# vsauce.net
KiCad netlist of a schematic drawn in EAGLE
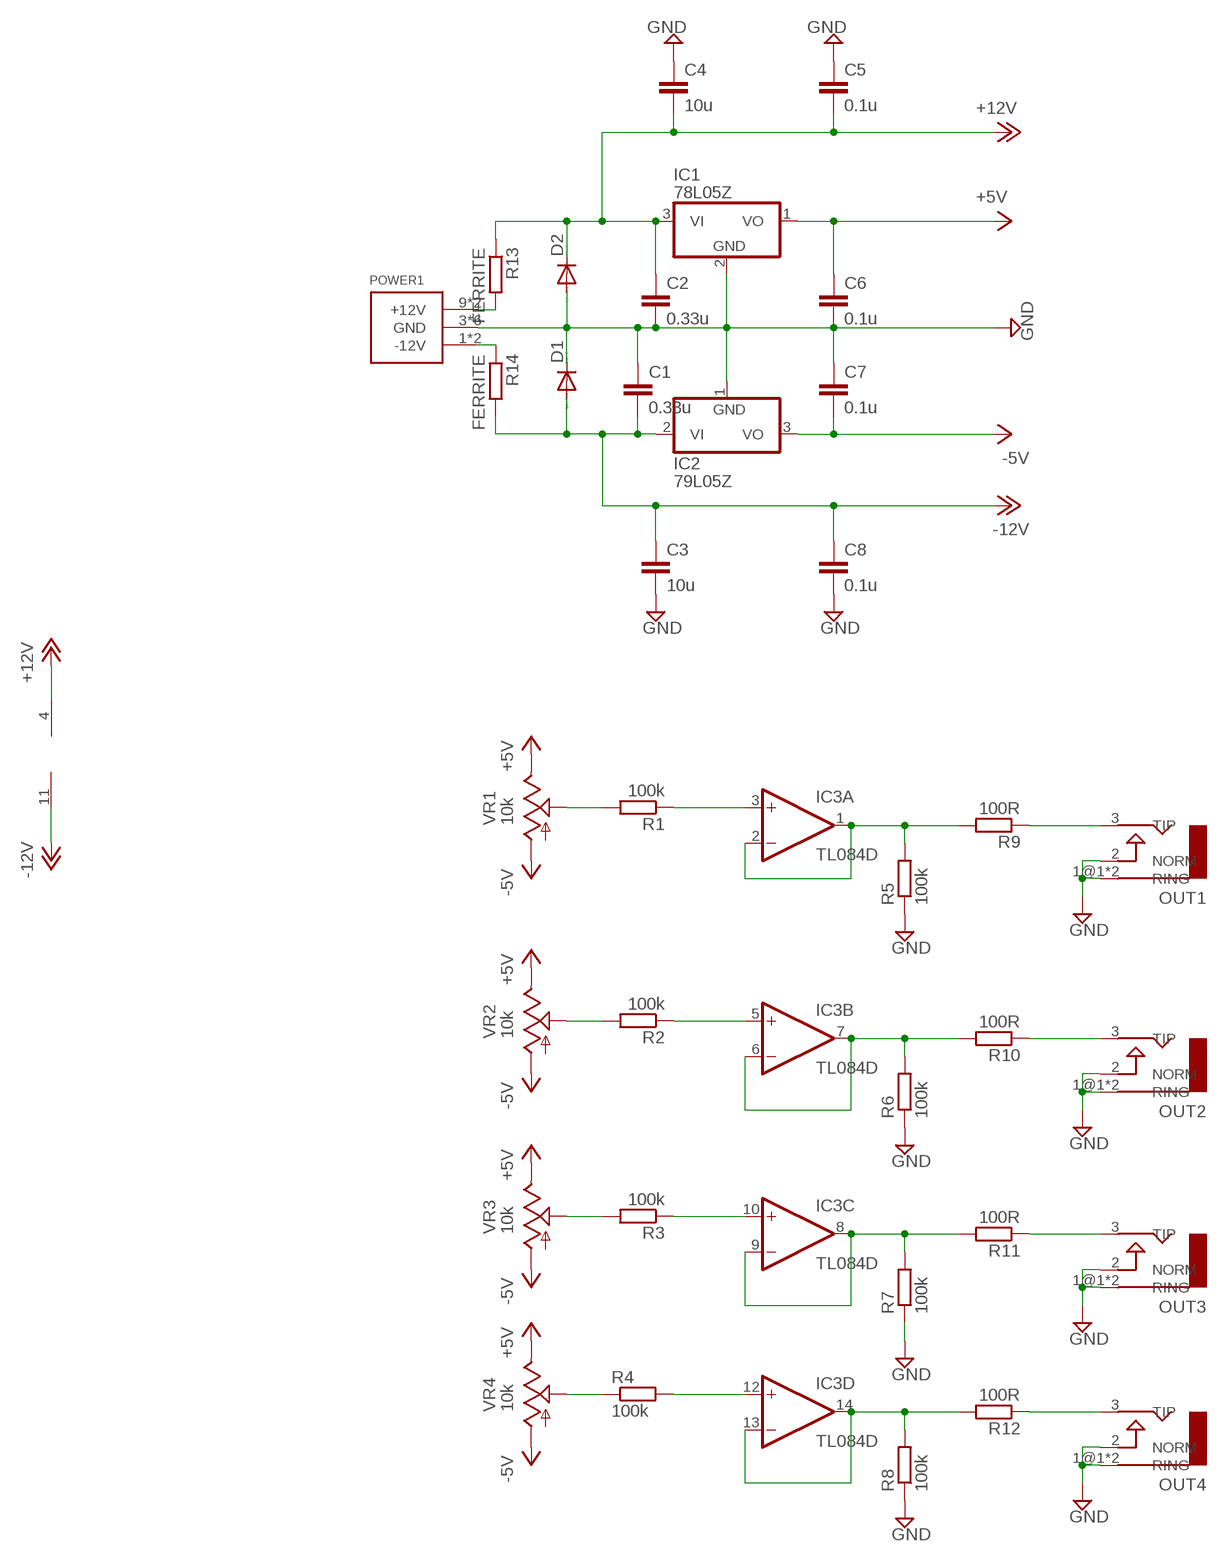
[diagram p0: schematic, sheet 1]

(export (version "E")
  (design (tool "Eeschema 10.0.6"))
  (components
    (comp (ref "C1")
      (value "0.33u")
      (footprint "eagle-import:C0805")
      (libsource (lib "eagle-import") (part "C-EUC0805"))
    )
    (comp (ref "C2")
      (value "0.33u")
      (footprint "eagle-import:C0805")
      (libsource (lib "eagle-import") (part "C-EUC0805"))
    )
    (comp (ref "C3")
      (value "10u")
      (footprint "eagle-import:C0805")
      (libsource (lib "eagle-import") (part "C-EUC0805"))
    )
    (comp (ref "C4")
      (value "10u")
      (footprint "eagle-import:C0805")
      (libsource (lib "eagle-import") (part "C-EUC0805"))
    )
    (comp (ref "C5")
      (value "0.1u")
      (footprint "eagle-import:C0805")
      (libsource (lib "eagle-import") (part "C-EUC0805"))
    )
    (comp (ref "C6")
      (value "0.1u")
      (footprint "eagle-import:C0805")
      (libsource (lib "eagle-import") (part "C-EUC0805"))
    )
    (comp (ref "C7")
      (value "0.1u")
      (footprint "eagle-import:C0805")
      (libsource (lib "eagle-import") (part "C-EUC0805"))
    )
    (comp (ref "C8")
      (value "0.1u")
      (footprint "eagle-import:C0805")
      (libsource (lib "eagle-import") (part "C-EUC0805"))
    )
    (comp (ref "D1")
      (value "DIODE-SOD323-W")
      (footprint "eagle-import:SOD323-W")
      (libsource (lib "eagle-import") (part "DIODE-SOD323-W"))
    )
    (comp (ref "D2")
      (value "DIODE-SOD323-W")
      (footprint "eagle-import:SOD323-W")
      (libsource (lib "eagle-import") (part "DIODE-SOD323-W"))
    )
    (comp (ref "IC1")
      (value "78L05Z")
      (footprint "eagle-import:TO92")
      (libsource (lib "eagle-import") (part "78ZL05"))
    )
    (comp (ref "IC2")
      (value "79L05Z")
      (footprint "eagle-import:TO92")
      (libsource (lib "eagle-import") (part "79L05"))
    )
    (comp (ref "IC3")
      (value "TL084D")
      (footprint "eagle-import:SO14")
      (libsource (lib "eagle-import") (part "TL084D"))
    )
    (comp (ref "OUT1")
      (value "V1")
      (footprint "eagle-import:ERTHENVAR-JACK")
      (libsource (lib "eagle-import") (part "AUDIO-JACKERTHENVAR"))
    )
    (comp (ref "OUT2")
      (value "V2")
      (footprint "eagle-import:ERTHENVAR-JACK")
      (libsource (lib "eagle-import") (part "AUDIO-JACKERTHENVAR"))
    )
    (comp (ref "OUT3")
      (value "V3")
      (footprint "eagle-import:ERTHENVAR-JACK")
      (libsource (lib "eagle-import") (part "AUDIO-JACKERTHENVAR"))
    )
    (comp (ref "OUT4")
      (value "V4")
      (footprint "eagle-import:ERTHENVAR-JACK")
      (libsource (lib "eagle-import") (part "AUDIO-JACKERTHENVAR"))
    )
    (comp (ref "POWER1")
      (value "POWER_SIMPLE10")
      (footprint "eagle-import:POWER_10")
      (libsource (lib "eagle-import") (part "POWER_SIMPLE10"))
    )
    (comp (ref "R1")
      (value "100k")
      (footprint "eagle-import:R0805")
      (libsource (lib "eagle-import") (part "R-EU_R0805"))
    )
    (comp (ref "R2")
      (value "100k")
      (footprint "eagle-import:R0805")
      (libsource (lib "eagle-import") (part "R-EU_R0805"))
    )
    (comp (ref "R3")
      (value "100k")
      (footprint "eagle-import:R0805")
      (libsource (lib "eagle-import") (part "R-EU_R0805"))
    )
    (comp (ref "R4")
      (value "100k")
      (footprint "eagle-import:R0805")
      (libsource (lib "eagle-import") (part "R-EU_R0805"))
    )
    (comp (ref "R5")
      (value "100k")
      (footprint "eagle-import:R0805")
      (libsource (lib "eagle-import") (part "R-EU_R0805"))
    )
    (comp (ref "R6")
      (value "100k")
      (footprint "eagle-import:R0805")
      (libsource (lib "eagle-import") (part "R-EU_R0805"))
    )
    (comp (ref "R7")
      (value "100k")
      (footprint "eagle-import:R0805")
      (libsource (lib "eagle-import") (part "R-EU_R0805"))
    )
    (comp (ref "R8")
      (value "100k")
      (footprint "eagle-import:R0805")
      (libsource (lib "eagle-import") (part "R-EU_R0805"))
    )
    (comp (ref "R9")
      (value "100R")
      (footprint "eagle-import:R0805")
      (libsource (lib "eagle-import") (part "R-EU_R0805"))
    )
    (comp (ref "R10")
      (value "100R")
      (footprint "eagle-import:R0805")
      (libsource (lib "eagle-import") (part "R-EU_R0805"))
    )
    (comp (ref "R11")
      (value "100R")
      (footprint "eagle-import:R0805")
      (libsource (lib "eagle-import") (part "R-EU_R0805"))
    )
    (comp (ref "R12")
      (value "100R")
      (footprint "eagle-import:R0805")
      (libsource (lib "eagle-import") (part "R-EU_R0805"))
    )
    (comp (ref "R13")
      (value "FERRITE")
      (footprint "eagle-import:R0805")
      (libsource (lib "eagle-import") (part "R-EU_R0805"))
    )
    (comp (ref "R14")
      (value "FERRITE")
      (footprint "eagle-import:R0805")
      (libsource (lib "eagle-import") (part "R-EU_R0805"))
    )
    (comp (ref "VR1")
      (value "10k")
      (footprint "eagle-import:9MM_SNAP-IN_POT")
      (libsource (lib "eagle-import") (part "9MM_SNAP-IN_POT_"))
    )
    (comp (ref "VR2")
      (value "10k")
      (footprint "eagle-import:9MM_SNAP-IN_POT")
      (libsource (lib "eagle-import") (part "9MM_SNAP-IN_POT_"))
    )
    (comp (ref "VR3")
      (value "10k")
      (footprint "eagle-import:9MM_SNAP-IN_POT")
      (libsource (lib "eagle-import") (part "9MM_SNAP-IN_POT_"))
    )
    (comp (ref "VR4")
      (value "10k")
      (footprint "eagle-import:9MM_SNAP-IN_POT")
      (libsource (lib "eagle-import") (part "9MM_SNAP-IN_POT_"))
    )
  )
  (nets
    (net (code "1") (name "+5V") (class "Default")
      (node (ref "C6") (pin "1") (pinfunction "1_1") (pintype "passive"))
      (node (ref "IC1") (pin "1") (pinfunction "VO_1") (pintype "passive"))
      (node (ref "VR1") (pin "3") (pinfunction "E_3") (pintype "passive"))
      (node (ref "VR2") (pin "3") (pinfunction "E_3") (pintype "passive"))
      (node (ref "VR3") (pin "3") (pinfunction "E_3") (pintype "passive"))
      (node (ref "VR4") (pin "3") (pinfunction "E_3") (pintype "passive"))
    )
    (net (code "2") (name "+12V") (class "Default")
      (node (ref "C2") (pin "1") (pinfunction "1_1") (pintype "passive"))
      (node (ref "C4") (pin "2") (pinfunction "2_2") (pintype "passive"))
      (node (ref "C5") (pin "2") (pinfunction "2_2") (pintype "passive"))
      (node (ref "D2") (pin "C") (pinfunction "C_C") (pintype "passive"))
      (node (ref "IC1") (pin "3") (pinfunction "VI_3") (pintype "input"))
      (node (ref "IC3") (pin "4") (pinfunction "V+_4") (pintype "power_in"))
      (node (ref "R13") (pin "1") (pinfunction "1_1") (pintype "passive"))
    )
    (net (code "3") (name "-5V") (class "Default")
      (node (ref "C7") (pin "2") (pinfunction "2_2") (pintype "passive"))
      (node (ref "IC2") (pin "3") (pinfunction "VO_3") (pintype "passive"))
      (node (ref "VR1") (pin "1") (pinfunction "A_1") (pintype "passive"))
      (node (ref "VR2") (pin "1") (pinfunction "A_1") (pintype "passive"))
      (node (ref "VR3") (pin "1") (pinfunction "A_1") (pintype "passive"))
      (node (ref "VR4") (pin "1") (pinfunction "A_1") (pintype "passive"))
    )
    (net (code "4") (name "-12V") (class "Default")
      (node (ref "C1") (pin "2") (pinfunction "2_2") (pintype "passive"))
      (node (ref "C3") (pin "1") (pinfunction "1_1") (pintype "passive"))
      (node (ref "C8") (pin "1") (pinfunction "1_1") (pintype "passive"))
      (node (ref "D1") (pin "A") (pinfunction "A_A") (pintype "passive"))
      (node (ref "IC2") (pin "2") (pinfunction "VI_2") (pintype "input"))
      (node (ref "IC3") (pin "11") (pinfunction "V-_11") (pintype "power_in"))
      (node (ref "R14") (pin "2") (pinfunction "2_2") (pintype "passive"))
    )
    (net (code "5") (name "GND") (class "Default")
      (node (ref "C1") (pin "1") (pinfunction "1_1") (pintype "passive"))
      (node (ref "C2") (pin "2") (pinfunction "2_2") (pintype "passive"))
      (node (ref "C3") (pin "2") (pinfunction "2_2") (pintype "passive"))
      (node (ref "C4") (pin "1") (pinfunction "1_1") (pintype "passive"))
      (node (ref "C5") (pin "1") (pinfunction "1_1") (pintype "passive"))
      (node (ref "C6") (pin "2") (pinfunction "2_2") (pintype "passive"))
      (node (ref "C7") (pin "1") (pinfunction "1_1") (pintype "passive"))
      (node (ref "C8") (pin "2") (pinfunction "2_2") (pintype "passive"))
      (node (ref "D1") (pin "C") (pinfunction "C_C") (pintype "passive"))
      (node (ref "D2") (pin "A") (pinfunction "A_A") (pintype "passive"))
      (node (ref "IC1") (pin "2") (pinfunction "GND_2") (pintype "passive"))
      (node (ref "IC2") (pin "1") (pinfunction "GND_1") (pintype "passive"))
      (node (ref "OUT1") (pin "1@1") (pinfunction "RING_1@1") (pintype "bidirectional"))
      (node (ref "OUT1") (pin "1@2") (pinfunction "RING_1@2") (pintype "bidirectional"))
      (node (ref "OUT1") (pin "2") (pinfunction "NORM_2") (pintype "bidirectional"))
      (node (ref "OUT2") (pin "1@1") (pinfunction "RING_1@1") (pintype "bidirectional"))
      (node (ref "OUT2") (pin "1@2") (pinfunction "RING_1@2") (pintype "bidirectional"))
      (node (ref "OUT2") (pin "2") (pinfunction "NORM_2") (pintype "bidirectional"))
      (node (ref "OUT3") (pin "1@1") (pinfunction "RING_1@1") (pintype "bidirectional"))
      (node (ref "OUT3") (pin "1@2") (pinfunction "RING_1@2") (pintype "bidirectional"))
      (node (ref "OUT3") (pin "2") (pinfunction "NORM_2") (pintype "bidirectional"))
      (node (ref "OUT4") (pin "1@1") (pinfunction "RING_1@1") (pintype "bidirectional"))
      (node (ref "OUT4") (pin "1@2") (pinfunction "RING_1@2") (pintype "bidirectional"))
      (node (ref "OUT4") (pin "2") (pinfunction "NORM_2") (pintype "bidirectional"))
      (node (ref "POWER1") (pin "3") (pinfunction "GND_3") (pintype "bidirectional"))
      (node (ref "POWER1") (pin "4") (pinfunction "GND_4") (pintype "bidirectional"))
      (node (ref "POWER1") (pin "5") (pinfunction "GND_5") (pintype "bidirectional"))
      (node (ref "POWER1") (pin "6") (pinfunction "GND_6") (pintype "bidirectional"))
      (node (ref "POWER1") (pin "7") (pinfunction "GND_7") (pintype "bidirectional"))
      (node (ref "POWER1") (pin "8") (pinfunction "GND_8") (pintype "bidirectional"))
      (node (ref "R5") (pin "1") (pinfunction "1_1") (pintype "passive"))
      (node (ref "R6") (pin "1") (pinfunction "1_1") (pintype "passive"))
      (node (ref "R7") (pin "1") (pinfunction "1_1") (pintype "passive"))
      (node (ref "R8") (pin "1") (pinfunction "1_1") (pintype "passive"))
    )
    (net (code "6") (name "Net-(IC3A-+IN)") (class "Default")
      (node (ref "IC3") (pin "3") (pinfunction "+IN_3") (pintype "input"))
      (node (ref "R1") (pin "1") (pinfunction "1_1") (pintype "passive"))
    )
    (net (code "7") (name "Net-(IC3A--IN)") (class "Default")
      (node (ref "IC3") (pin "1") (pinfunction "OUT_1") (pintype "output"))
      (node (ref "IC3") (pin "2") (pinfunction "-IN_2") (pintype "input"))
      (node (ref "R5") (pin "2") (pinfunction "2_2") (pintype "passive"))
      (node (ref "R9") (pin "2") (pinfunction "2_2") (pintype "passive"))
    )
    (net (code "8") (name "Net-(IC3B-+IN)") (class "Default")
      (node (ref "IC3") (pin "5") (pinfunction "+IN_5") (pintype "input"))
      (node (ref "R2") (pin "1") (pinfunction "1_1") (pintype "passive"))
    )
    (net (code "9") (name "Net-(IC3B--IN)") (class "Default")
      (node (ref "IC3") (pin "6") (pinfunction "-IN_6") (pintype "input"))
      (node (ref "IC3") (pin "7") (pinfunction "OUT_7") (pintype "output"))
      (node (ref "R10") (pin "2") (pinfunction "2_2") (pintype "passive"))
      (node (ref "R6") (pin "2") (pinfunction "2_2") (pintype "passive"))
    )
    (net (code "10") (name "Net-(IC3C-+IN)") (class "Default")
      (node (ref "IC3") (pin "10") (pinfunction "+IN_10") (pintype "input"))
      (node (ref "R3") (pin "1") (pinfunction "1_1") (pintype "passive"))
    )
    (net (code "11") (name "Net-(IC3C--IN)") (class "Default")
      (node (ref "IC3") (pin "8") (pinfunction "OUT_8") (pintype "output"))
      (node (ref "IC3") (pin "9") (pinfunction "-IN_9") (pintype "input"))
      (node (ref "R11") (pin "2") (pinfunction "2_2") (pintype "passive"))
      (node (ref "R7") (pin "2") (pinfunction "2_2") (pintype "passive"))
    )
    (net (code "12") (name "Net-(IC3D-+IN)") (class "Default")
      (node (ref "IC3") (pin "12") (pinfunction "+IN_12") (pintype "input"))
      (node (ref "R4") (pin "2") (pinfunction "2_2") (pintype "passive"))
    )
    (net (code "13") (name "Net-(IC3D--IN)") (class "Default")
      (node (ref "IC3") (pin "13") (pinfunction "-IN_13") (pintype "input"))
      (node (ref "IC3") (pin "14") (pinfunction "OUT_14") (pintype "output"))
      (node (ref "R12") (pin "2") (pinfunction "2_2") (pintype "passive"))
      (node (ref "R8") (pin "2") (pinfunction "2_2") (pintype "passive"))
    )
    (net (code "14") (name "Net-(OUT1-TIP)") (class "Default")
      (node (ref "OUT1") (pin "3") (pinfunction "TIP_3") (pintype "bidirectional"))
      (node (ref "R9") (pin "1") (pinfunction "1_1") (pintype "passive"))
    )
    (net (code "15") (name "Net-(OUT2-TIP)") (class "Default")
      (node (ref "OUT2") (pin "3") (pinfunction "TIP_3") (pintype "bidirectional"))
      (node (ref "R10") (pin "1") (pinfunction "1_1") (pintype "passive"))
    )
    (net (code "16") (name "Net-(OUT3-TIP)") (class "Default")
      (node (ref "OUT3") (pin "3") (pinfunction "TIP_3") (pintype "bidirectional"))
      (node (ref "R11") (pin "1") (pinfunction "1_1") (pintype "passive"))
    )
    (net (code "17") (name "Net-(OUT4-TIP)") (class "Default")
      (node (ref "OUT4") (pin "3") (pinfunction "TIP_3") (pintype "bidirectional"))
      (node (ref "R12") (pin "1") (pinfunction "1_1") (pintype "passive"))
    )
    (net (code "18") (name "Net-(POWER1-+12V-Pad10)") (class "Default")
      (node (ref "POWER1") (pin "10") (pinfunction "+12V_10") (pintype "bidirectional"))
      (node (ref "POWER1") (pin "9") (pinfunction "+12V_9") (pintype "bidirectional"))
      (node (ref "R13") (pin "2") (pinfunction "2_2") (pintype "passive"))
    )
    (net (code "19") (name "Net-(POWER1--12V-Pad1)") (class "Default")
      (node (ref "POWER1") (pin "1") (pinfunction "-12V_1") (pintype "bidirectional"))
      (node (ref "POWER1") (pin "2") (pinfunction "-12V_2") (pintype "bidirectional"))
      (node (ref "R14") (pin "1") (pinfunction "1_1") (pintype "passive"))
    )
    (net (code "20") (name "Net-(VR1-S)") (class "Default")
      (node (ref "R1") (pin "2") (pinfunction "2_2") (pintype "passive"))
      (node (ref "VR1") (pin "2") (pinfunction "S_2") (pintype "passive"))
    )
    (net (code "21") (name "Net-(VR2-S)") (class "Default")
      (node (ref "R2") (pin "2") (pinfunction "2_2") (pintype "passive"))
      (node (ref "VR2") (pin "2") (pinfunction "S_2") (pintype "passive"))
    )
    (net (code "22") (name "Net-(VR3-S)") (class "Default")
      (node (ref "R3") (pin "2") (pinfunction "2_2") (pintype "passive"))
      (node (ref "VR3") (pin "2") (pinfunction "S_2") (pintype "passive"))
    )
    (net (code "23") (name "Net-(VR4-S)") (class "Default")
      (node (ref "R4") (pin "1") (pinfunction "1_1") (pintype "passive"))
      (node (ref "VR4") (pin "2") (pinfunction "S_2") (pintype "passive"))
    )
  )
)
